# MAIN.net
KiCad netlist of a schematic drawn in Altium Designer
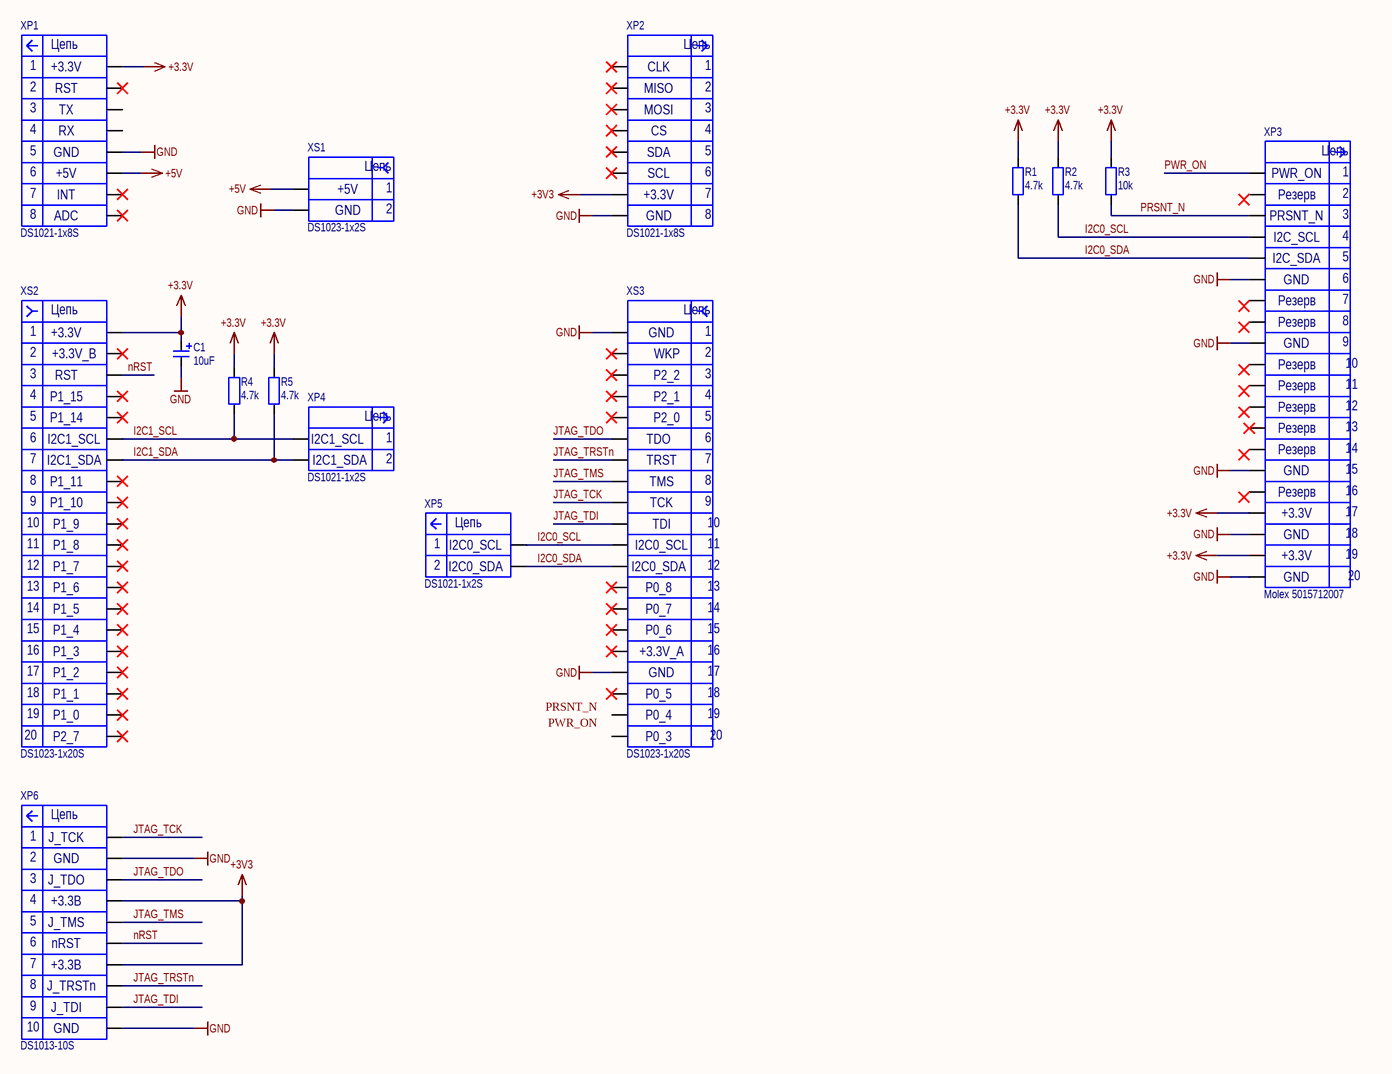
[diagram p0: MAIN.SchDoc]

(export (version "E")
  (design (tool "Eeschema 10.0.6"))
  (components
    (comp (ref "C1")
      (value "10uF")
      (footprint "CAP ALSMD ELEC 4.3MM H5.4MM")
      (description "Конденсатор К50-97 – 25В – 10мкФ (±20) % – ЕВАЯ.673541.054ТУ")
      (fields
        (field (name "MANUFACTURER PART NUMBER") "К50-97 – 25В – 10мкФ (±20) % – ЕВАЯ.673541.054ТУ")
        (field (name "TOLERANCE") "± 20%")
      )
      (libsource (lib "ComponentsDb") (part "Capacitor_Polar"))
    )
    (comp (ref "R1")
      (value "4.7k")
      (footprint "RES 0603_1608")
      (description "Резистор 0603-0,1Вт-4.7кОм ± 1%")
      (fields (field (name "MANUFACTURER PART NUMBER") "RC0603FR-074K7L") (field (name "TOLERANCE") "± 1%"))
      (libsource (lib "ComponentsDb") (part "Resistor_b"))
    )
    (comp (ref "R2")
      (value "4.7k")
      (footprint "RES 0603_1608")
      (description "Резистор 0603-0,1Вт-4.7кОм ± 1%")
      (fields (field (name "MANUFACTURER PART NUMBER") "RC0603FR-074K7L") (field (name "TOLERANCE") "± 1%"))
      (libsource (lib "ComponentsDb") (part "Resistor_b"))
    )
    (comp (ref "R3")
      (value "10k")
      (footprint "RES 0603_1608")
      (description "Резистор 0603-0,1Вт-10кОм ± 1%")
      (fields (field (name "MANUFACTURER PART NUMBER") "RC0603FR-0710KL") (field (name "TOLERANCE") "± 1%"))
      (libsource (lib "ComponentsDb") (part "Resistor_b"))
    )
    (comp (ref "R4")
      (value "4.7k")
      (footprint "RES 0603_1608")
      (description "Резистор 0603-0,1Вт-4.7кОм ± 1%")
      (fields (field (name "MANUFACTURER PART NUMBER") "RC0603FR-074K7L") (field (name "TOLERANCE") "± 1%"))
      (libsource (lib "ComponentsDb") (part "Resistor_b"))
    )
    (comp (ref "R5")
      (value "4.7k")
      (footprint "RES 0603_1608")
      (description "Резистор 0603-0,1Вт-4.7кОм ± 1%")
      (fields (field (name "MANUFACTURER PART NUMBER") "RC0603FR-074K7L") (field (name "TOLERANCE") "± 1%"))
      (libsource (lib "ComponentsDb") (part "Resistor_b"))
    )
    (comp (ref "XP1")
      (value "DS1021-1x8S")
      (footprint "DS1021-1x8S")
      (description "Соединитель DS1021-1x8S")
      (fields
        (field (name "NET_8") "ADC")
        (field (name "NET_7") "INT")
        (field (name "NET_6") "+5V")
        (field (name "NET_5") "GND")
        (field (name "NET_4") "RX")
        (field (name "NET_3") "TX")
        (field (name "NET_2") "RST")
        (field (name "NET_1") "+3.3V")
        (field (name "MANUFACTURER") "Connfly")
      )
      (libsource (lib "ComponentsDb") (part "Plug_8pin"))
    )
    (comp (ref "XP2")
      (value "DS1021-1x8S")
      (footprint "DS1021-1x8S")
      (description "Соединитель DS1021-1x8S")
      (fields
        (field (name "NET_8") "GND")
        (field (name "NET_7") "+3.3V")
        (field (name "NET_6") "SCL")
        (field (name "NET_5") "SDA")
        (field (name "NET_4") "CS")
        (field (name "NET_3") "MOSI")
        (field (name "NET_2") "MISO")
        (field (name "NET_1") "CLK")
        (field (name "MANUFACTURER") "Connfly")
      )
      (libsource (lib "ComponentsDb") (part "Plug_8pin"))
    )
    (comp (ref "XP3")
      (value "Molex 5015712007")
      (footprint "Molex 5015712007")
      (description "Соединитель Molex 5015712007")
      (fields
        (field (name "NET_20") "GND")
        (field (name "NET_19") "+3.3V")
        (field (name "NET_18") "GND")
        (field (name "NET_17") "+3.3V")
        (field (name "NET_16") "Резерв")
        (field (name "NET_15") "GND")
        (field (name "NET_14") "Резерв")
        (field (name "NET_13") "Резерв")
        (field (name "NET_12") "Резерв")
        (field (name "NET_11") "Резерв")
        (field (name "NET_10") "Резерв")
        (field (name "NET_9") "GND")
        (field (name "NET_8") "Резерв")
        (field (name "NET_7") "Резерв")
        (field (name "NET_6") "GND")
        (field (name "NET_5") "I2C_SDA")
        (field (name "NET_4") "I2C_SCL")
        (field (name "NET_3") "PRSNT_N")
        (field (name "NET_2") "Резерв")
        (field (name "NET_1") "PWR_ON")
        (field (name "MANUFACTURER") "Molex")
      )
      (libsource (lib "ComponentsDb") (part "Plug_20pin"))
    )
    (comp (ref "XP4")
      (value "DS1021-1x2S")
      (footprint "DS1021-1x2S")
      (description "Соединитель DS1021-1x2S")
      (fields
        (field (name "NET_2") "I2C1_SDA")
        (field (name "NET_1") "I2C1_SCL")
        (field (name "MANUFACTURER") "Connfly")
      )
      (libsource (lib "ComponentsDb") (part "Plug_2pin"))
    )
    (comp (ref "XP5")
      (value "DS1021-1x2S")
      (footprint "DS1021-1x2S")
      (description "Соединитель DS1021-1x2S")
      (fields
        (field (name "NET_2") "I2C0_SDA")
        (field (name "NET_1") "I2C0_SCL")
        (field (name "MANUFACTURER") "Connfly")
      )
      (libsource (lib "ComponentsDb") (part "Plug_2pin"))
    )
    (comp (ref "XP6")
      (value "DS1013-10S")
      (footprint "DS1013-10S")
      (description "Соединитель DS1013-10S")
      (fields
        (field (name "MANUFACTURER") "Connfly")
        (field (name "NET_10") "GND")
        (field (name "NET_9") "J_TDI")
        (field (name "NET_8") "J_TRSTn")
        (field (name "NET_7") "+3.3В")
        (field (name "NET_6") "nRST")
        (field (name "NET_5") "J_TMS")
        (field (name "NET_4") "+3.3В")
        (field (name "NET_3") "J_TDO")
        (field (name "NET_2") "GND")
        (field (name "NET_1") "J_TCK")
      )
      (libsource (lib "ComponentsDb") (part "Plug_10pin"))
    )
    (comp (ref "XS1")
      (value "DS1023-1x2S")
      (footprint "DS1023-1x2S")
      (description "Соединитель DS1023-1x2S")
      (fields
        (field (name "NET_2") "GND")
        (field (name "NET_1") "+5V")
        (field (name "MANUFACTURER") "Connfly")
      )
      (libsource (lib "ComponentsDb") (part "Socket_2pin"))
    )
    (comp (ref "XS2")
      (value "DS1023-1x20S")
      (footprint "DS1023-1x20S")
      (description "Соединитель DS1023-1x20S")
      (fields
        (field (name "NET_20") "P2_7")
        (field (name "NET_19") "P1_0")
        (field (name "NET_18") "P1_1")
        (field (name "NET_17") "P1_2")
        (field (name "NET_16") "P1_3")
        (field (name "NET_15") "P1_4")
        (field (name "NET_14") "P1_5")
        (field (name "NET_13") "P1_6")
        (field (name "NET_12") "P1_7")
        (field (name "NET_11") "P1_8")
        (field (name "NET_10") "P1_9")
        (field (name "NET_9") "P1_10")
        (field (name "NET_8") "P1_11")
        (field (name "NET_7") "I2C1_SDA")
        (field (name "NET_6") "I2C1_SCL")
        (field (name "NET_5") "P1_14")
        (field (name "NET_4") "P1_15")
        (field (name "NET_3") "RST")
        (field (name "NET_2") "+3.3V_B")
        (field (name "NET_1") "+3.3V")
        (field (name "MANUFACTURER") "Connfly")
      )
      (libsource (lib "ComponentsDb") (part "Socket_20pin"))
    )
    (comp (ref "XS3")
      (value "DS1023-1x20S")
      (footprint "DS1023-1x20S")
      (description "Соединитель DS1023-1x20S")
      (fields
        (field (name "NET_20") "P0_3")
        (field (name "NET_19") "P0_4")
        (field (name "NET_18") "P0_5")
        (field (name "NET_17") "GND")
        (field (name "NET_16") "+3.3V_A")
        (field (name "NET_15") "P0_6")
        (field (name "NET_14") "P0_7")
        (field (name "NET_13") "P0_8")
        (field (name "NET_12") "I2C0_SDA")
        (field (name "NET_11") "I2C0_SCL")
        (field (name "NET_10") "TDI")
        (field (name "NET_9") "TCK")
        (field (name "NET_8") "TMS")
        (field (name "NET_7") "TRST")
        (field (name "NET_6") "TDO")
        (field (name "NET_5") "P2_0")
        (field (name "NET_4") "P2_1")
        (field (name "NET_3") "P2_2")
        (field (name "NET_2") "WKP")
        (field (name "NET_1") "GND")
        (field (name "MANUFACTURER") "Connfly")
      )
      (libsource (lib "ComponentsDb") (part "Socket_20pin"))
    )
  )
  (nets
    (net (code "1") (name "+3.3V") (class "Default")
      (node (ref "C1") (pin "1") (pinfunction "P_1") (pintype "passive"))
      (node (ref "R1") (pin "2") (pinfunction "2_2") (pintype "passive"))
      (node (ref "R2") (pin "2") (pinfunction "2_2") (pintype "passive"))
      (node (ref "R3") (pin "2") (pinfunction "2_2") (pintype "passive"))
      (node (ref "R4") (pin "2") (pinfunction "2_2") (pintype "passive"))
      (node (ref "R5") (pin "2") (pinfunction "2_2") (pintype "passive"))
      (node (ref "XP1") (pin "1") (pinfunction "1_1") (pintype "passive"))
      (node (ref "XP3") (pin "17") (pinfunction "17_17") (pintype "passive"))
      (node (ref "XP3") (pin "19") (pinfunction "19_19") (pintype "passive"))
      (node (ref "XS2") (pin "1") (pinfunction "1_1") (pintype "passive"))
    )
    (net (code "2") (name "+3V3") (class "Default")
      (node (ref "XP2") (pin "7") (pinfunction "7_7") (pintype "passive"))
      (node (ref "XP6") (pin "4") (pinfunction "4_4") (pintype "passive"))
      (node (ref "XP6") (pin "7") (pinfunction "7_7") (pintype "passive"))
    )
    (net (code "3") (name "+5V") (class "Default")
      (node (ref "XP1") (pin "6") (pinfunction "6_6") (pintype "passive"))
      (node (ref "XS1") (pin "1") (pinfunction "1_1") (pintype "passive"))
    )
    (net (code "4") (name "/I2C0_SCL") (class "Default")
      (node (ref "R2") (pin "1") (pinfunction "1_1") (pintype "passive"))
      (node (ref "XP3") (pin "4") (pinfunction "4_4") (pintype "passive"))
      (node (ref "XP5") (pin "1") (pinfunction "1_1") (pintype "passive"))
      (node (ref "XS3") (pin "11") (pinfunction "11_11") (pintype "passive"))
    )
    (net (code "5") (name "/I2C0_SDA") (class "Default")
      (node (ref "R1") (pin "1") (pinfunction "1_1") (pintype "passive"))
      (node (ref "XP3") (pin "5") (pinfunction "5_5") (pintype "passive"))
      (node (ref "XP5") (pin "2") (pinfunction "2_2") (pintype "passive"))
      (node (ref "XS3") (pin "12") (pinfunction "12_12") (pintype "passive"))
    )
    (net (code "6") (name "/I2C1_SCL") (class "Default")
      (node (ref "R4") (pin "1") (pinfunction "1_1") (pintype "passive"))
      (node (ref "XP4") (pin "1") (pinfunction "1_1") (pintype "passive"))
      (node (ref "XS2") (pin "6") (pinfunction "6_6") (pintype "passive"))
    )
    (net (code "7") (name "/I2C1_SDA") (class "Default")
      (node (ref "R5") (pin "1") (pinfunction "1_1") (pintype "passive"))
      (node (ref "XP4") (pin "2") (pinfunction "2_2") (pintype "passive"))
      (node (ref "XS2") (pin "7") (pinfunction "7_7") (pintype "passive"))
    )
    (net (code "8") (name "/JTAG_TCK") (class "Default")
      (node (ref "XP6") (pin "1") (pinfunction "1_1") (pintype "passive"))
      (node (ref "XS3") (pin "9") (pinfunction "9_9") (pintype "passive"))
    )
    (net (code "9") (name "/JTAG_TDI") (class "Default")
      (node (ref "XP6") (pin "9") (pinfunction "9_9") (pintype "passive"))
      (node (ref "XS3") (pin "10") (pinfunction "10_10") (pintype "passive"))
    )
    (net (code "10") (name "/JTAG_TDO") (class "Default")
      (node (ref "XP6") (pin "3") (pinfunction "3_3") (pintype "passive"))
      (node (ref "XS3") (pin "6") (pinfunction "6_6") (pintype "passive"))
    )
    (net (code "11") (name "/JTAG_TMS") (class "Default")
      (node (ref "XP6") (pin "5") (pinfunction "5_5") (pintype "passive"))
      (node (ref "XS3") (pin "8") (pinfunction "8_8") (pintype "passive"))
    )
    (net (code "12") (name "/JTAG_TRSTn") (class "Default")
      (node (ref "XP6") (pin "8") (pinfunction "8_8") (pintype "passive"))
      (node (ref "XS3") (pin "7") (pinfunction "7_7") (pintype "passive"))
    )
    (net (code "13") (name "/PRSNT_N") (class "Default")
      (node (ref "R3") (pin "1") (pinfunction "1_1") (pintype "passive"))
      (node (ref "XP3") (pin "3") (pinfunction "3_3") (pintype "passive"))
    )
    (net (code "14") (name "/PWR_ON") (class "Default")
      (node (ref "XP3") (pin "1") (pinfunction "1_1") (pintype "passive"))
    )
    (net (code "15") (name "/nRST") (class "Default")
      (node (ref "XP6") (pin "6") (pinfunction "6_6") (pintype "passive"))
      (node (ref "XS2") (pin "3") (pinfunction "3_3") (pintype "passive"))
    )
    (net (code "16") (name "GND") (class "Default")
      (node (ref "C1") (pin "2") (pinfunction "N_2") (pintype "passive"))
      (node (ref "XP1") (pin "5") (pinfunction "5_5") (pintype "passive"))
      (node (ref "XP2") (pin "8") (pinfunction "8_8") (pintype "passive"))
      (node (ref "XP3") (pin "15") (pinfunction "15_15") (pintype "passive"))
      (node (ref "XP3") (pin "18") (pinfunction "18_18") (pintype "passive"))
      (node (ref "XP3") (pin "20") (pinfunction "20_20") (pintype "passive"))
      (node (ref "XP3") (pin "6") (pinfunction "6_6") (pintype "passive"))
      (node (ref "XP3") (pin "9") (pinfunction "9_9") (pintype "passive"))
      (node (ref "XP6") (pin "10") (pinfunction "10_10") (pintype "passive"))
      (node (ref "XP6") (pin "2") (pinfunction "2_2") (pintype "passive"))
      (node (ref "XS1") (pin "2") (pinfunction "2_2") (pintype "passive"))
      (node (ref "XS3") (pin "1") (pinfunction "1_1") (pintype "passive"))
      (node (ref "XS3") (pin "17") (pinfunction "17_17") (pintype "passive"))
    )
    (net (code "17") (name "unconnected-(XP1-Pad2)") (class "Default")
      (node (ref "XP1") (pin "2") (pinfunction "2_2") (pintype "passive+no_connect"))
    )
    (net (code "18") (name "unconnected-(XP1-Pad3)") (class "Default")
      (node (ref "XP1") (pin "3") (pinfunction "3_3") (pintype "passive"))
    )
    (net (code "19") (name "unconnected-(XP1-Pad4)") (class "Default")
      (node (ref "XP1") (pin "4") (pinfunction "4_4") (pintype "passive"))
    )
    (net (code "20") (name "unconnected-(XP1-Pad7)") (class "Default")
      (node (ref "XP1") (pin "7") (pinfunction "7_7") (pintype "passive+no_connect"))
    )
    (net (code "21") (name "unconnected-(XP1-Pad8)") (class "Default")
      (node (ref "XP1") (pin "8") (pinfunction "8_8") (pintype "passive+no_connect"))
    )
    (net (code "22") (name "unconnected-(XP2-Pad1)") (class "Default")
      (node (ref "XP2") (pin "1") (pinfunction "1_1") (pintype "passive+no_connect"))
    )
    (net (code "23") (name "unconnected-(XP2-Pad2)") (class "Default")
      (node (ref "XP2") (pin "2") (pinfunction "2_2") (pintype "passive+no_connect"))
    )
    (net (code "24") (name "unconnected-(XP2-Pad3)") (class "Default")
      (node (ref "XP2") (pin "3") (pinfunction "3_3") (pintype "passive+no_connect"))
    )
    (net (code "25") (name "unconnected-(XP2-Pad4)") (class "Default")
      (node (ref "XP2") (pin "4") (pinfunction "4_4") (pintype "passive+no_connect"))
    )
    (net (code "26") (name "unconnected-(XP2-Pad5)") (class "Default")
      (node (ref "XP2") (pin "5") (pinfunction "5_5") (pintype "passive+no_connect"))
    )
    (net (code "27") (name "unconnected-(XP2-Pad6)") (class "Default")
      (node (ref "XP2") (pin "6") (pinfunction "6_6") (pintype "passive+no_connect"))
    )
    (net (code "28") (name "unconnected-(XP3-Pad2)") (class "Default")
      (node (ref "XP3") (pin "2") (pinfunction "2_2") (pintype "passive"))
    )
    (net (code "29") (name "unconnected-(XP3-Pad7)") (class "Default")
      (node (ref "XP3") (pin "7") (pinfunction "7_7") (pintype "passive"))
    )
    (net (code "30") (name "unconnected-(XP3-Pad8)") (class "Default")
      (node (ref "XP3") (pin "8") (pinfunction "8_8") (pintype "passive"))
    )
    (net (code "31") (name "unconnected-(XP3-Pad10)") (class "Default")
      (node (ref "XP3") (pin "10") (pinfunction "10_10") (pintype "passive"))
    )
    (net (code "32") (name "unconnected-(XP3-Pad11)") (class "Default")
      (node (ref "XP3") (pin "11") (pinfunction "11_11") (pintype "passive"))
    )
    (net (code "33") (name "unconnected-(XP3-Pad12)") (class "Default")
      (node (ref "XP3") (pin "12") (pinfunction "12_12") (pintype "passive"))
    )
    (net (code "34") (name "unconnected-(XP3-Pad13)") (class "Default")
      (node (ref "XP3") (pin "13") (pinfunction "13_13") (pintype "passive+no_connect"))
    )
    (net (code "35") (name "unconnected-(XP3-Pad14)") (class "Default")
      (node (ref "XP3") (pin "14") (pinfunction "14_14") (pintype "passive"))
    )
    (net (code "36") (name "unconnected-(XP3-Pad16)") (class "Default")
      (node (ref "XP3") (pin "16") (pinfunction "16_16") (pintype "passive"))
    )
    (net (code "37") (name "unconnected-(XS2-Pad2)") (class "Default")
      (node (ref "XS2") (pin "2") (pinfunction "2_2") (pintype "passive+no_connect"))
    )
    (net (code "38") (name "unconnected-(XS2-Pad4)") (class "Default")
      (node (ref "XS2") (pin "4") (pinfunction "4_4") (pintype "passive+no_connect"))
    )
    (net (code "39") (name "unconnected-(XS2-Pad5)") (class "Default")
      (node (ref "XS2") (pin "5") (pinfunction "5_5") (pintype "passive+no_connect"))
    )
    (net (code "40") (name "unconnected-(XS2-Pad8)") (class "Default")
      (node (ref "XS2") (pin "8") (pinfunction "8_8") (pintype "passive+no_connect"))
    )
    (net (code "41") (name "unconnected-(XS2-Pad9)") (class "Default")
      (node (ref "XS2") (pin "9") (pinfunction "9_9") (pintype "passive+no_connect"))
    )
    (net (code "42") (name "unconnected-(XS2-Pad10)") (class "Default")
      (node (ref "XS2") (pin "10") (pinfunction "10_10") (pintype "passive+no_connect"))
    )
    (net (code "43") (name "unconnected-(XS2-Pad11)") (class "Default")
      (node (ref "XS2") (pin "11") (pinfunction "11_11") (pintype "passive+no_connect"))
    )
    (net (code "44") (name "unconnected-(XS2-Pad12)") (class "Default")
      (node (ref "XS2") (pin "12") (pinfunction "12_12") (pintype "passive+no_connect"))
    )
    (net (code "45") (name "unconnected-(XS2-Pad13)") (class "Default")
      (node (ref "XS2") (pin "13") (pinfunction "13_13") (pintype "passive+no_connect"))
    )
    (net (code "46") (name "unconnected-(XS2-Pad14)") (class "Default")
      (node (ref "XS2") (pin "14") (pinfunction "14_14") (pintype "passive+no_connect"))
    )
    (net (code "47") (name "unconnected-(XS2-Pad15)") (class "Default")
      (node (ref "XS2") (pin "15") (pinfunction "15_15") (pintype "passive+no_connect"))
    )
    (net (code "48") (name "unconnected-(XS2-Pad16)") (class "Default")
      (node (ref "XS2") (pin "16") (pinfunction "16_16") (pintype "passive+no_connect"))
    )
    (net (code "49") (name "unconnected-(XS2-Pad17)") (class "Default")
      (node (ref "XS2") (pin "17") (pinfunction "17_17") (pintype "passive+no_connect"))
    )
    (net (code "50") (name "unconnected-(XS2-Pad18)") (class "Default")
      (node (ref "XS2") (pin "18") (pinfunction "18_18") (pintype "passive+no_connect"))
    )
    (net (code "51") (name "unconnected-(XS2-Pad19)") (class "Default")
      (node (ref "XS2") (pin "19") (pinfunction "19_19") (pintype "passive+no_connect"))
    )
    (net (code "52") (name "unconnected-(XS2-Pad20)") (class "Default")
      (node (ref "XS2") (pin "20") (pinfunction "20_20") (pintype "passive+no_connect"))
    )
    (net (code "53") (name "unconnected-(XS3-Pad2)") (class "Default")
      (node (ref "XS3") (pin "2") (pinfunction "2_2") (pintype "passive+no_connect"))
    )
    (net (code "54") (name "unconnected-(XS3-Pad3)") (class "Default")
      (node (ref "XS3") (pin "3") (pinfunction "3_3") (pintype "passive+no_connect"))
    )
    (net (code "55") (name "unconnected-(XS3-Pad4)") (class "Default")
      (node (ref "XS3") (pin "4") (pinfunction "4_4") (pintype "passive+no_connect"))
    )
    (net (code "56") (name "unconnected-(XS3-Pad5)") (class "Default")
      (node (ref "XS3") (pin "5") (pinfunction "5_5") (pintype "passive+no_connect"))
    )
    (net (code "57") (name "unconnected-(XS3-Pad13)") (class "Default")
      (node (ref "XS3") (pin "13") (pinfunction "13_13") (pintype "passive+no_connect"))
    )
    (net (code "58") (name "unconnected-(XS3-Pad14)") (class "Default")
      (node (ref "XS3") (pin "14") (pinfunction "14_14") (pintype "passive+no_connect"))
    )
    (net (code "59") (name "unconnected-(XS3-Pad15)") (class "Default")
      (node (ref "XS3") (pin "15") (pinfunction "15_15") (pintype "passive+no_connect"))
    )
    (net (code "60") (name "unconnected-(XS3-Pad16)") (class "Default")
      (node (ref "XS3") (pin "16") (pinfunction "16_16") (pintype "passive+no_connect"))
    )
    (net (code "61") (name "unconnected-(XS3-Pad18)") (class "Default")
      (node (ref "XS3") (pin "18") (pinfunction "18_18") (pintype "passive+no_connect"))
    )
    (net (code "62") (name "unconnected-(XS3-Pad19)") (class "Default")
      (node (ref "XS3") (pin "19") (pinfunction "19_19") (pintype "passive"))
    )
    (net (code "63") (name "unconnected-(XS3-Pad20)") (class "Default")
      (node (ref "XS3") (pin "20") (pinfunction "20_20") (pintype "passive"))
    )
  )
)
